# breakbeam-interface.net
KiCad netlist of a schematic drawn in Altium Designer
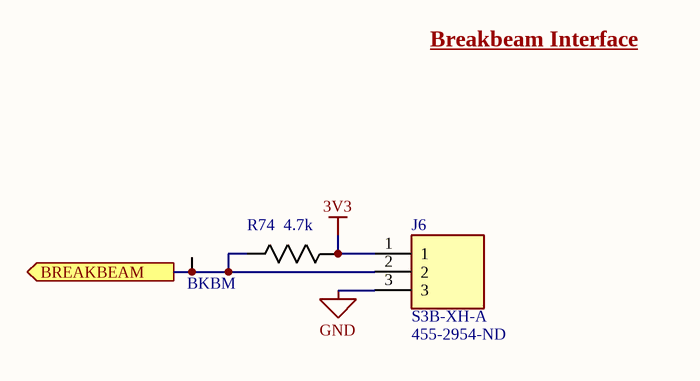
[diagram p0: breakbeam-interface.SchDoc]

(export (version "E")
  (design (tool "Eeschema 10.0.6"))
  (components
    (comp (ref "BKBM")
      (value "Test Point (Via)")
      (footprint "TP")
      (libsource (lib "IC_Library") (part "Test Point (Via)"))
    )
    (comp (ref "J6")
      (value "S3B-XH-A")
      (footprint "JST_S3B-XH-A")
      (description "Connector Header Through Hole Right Angle 3 position 0.098 (2.50mm)")
      (fields
        (field (name "MF") "JST Sales")
        (field (name "MP") "B3B-XH-A(LF)(SN)")
        (field (name "SUPPLIER PART NUMBER 1") "455-2954-ND")
      )
      (libsource (lib "Connector_Library") (part "CN HDR 3POS JST XH RA"))
    )
    (comp (ref "R74")
      (value "4.7k")
      (footprint "0603")
      (description "RES SMD 4.7k OHM 5% 1/8W 0603")
      (fields (field (name "TOLERANCE") "5%") (field (name "PART NUMBER") "RES 4.7k 1/8W - 5%"))
      (libsource (lib "Resistor_Library") (part "RES 4.7k 1/8W - 5%"))
    )
  )
  (nets
    (net (code "1") (name "/BREAKBEAM") (class "Default")
      (node (ref "BKBM") (pin "1") (pinfunction "1_1") (pintype "passive"))
      (node (ref "J6") (pin "2") (pinfunction "2_2") (pintype "passive"))
      (node (ref "R74") (pin "2") (pinfunction "R2_2") (pintype "passive"))
    )
    (net (code "2") (name "3V3") (class "Default")
      (node (ref "J6") (pin "1") (pinfunction "1_1") (pintype "passive"))
      (node (ref "R74") (pin "1") (pinfunction "R1_1") (pintype "passive"))
    )
    (net (code "3") (name "GND") (class "Default")
      (node (ref "J6") (pin "3") (pinfunction "3_3") (pintype "passive"))
    )
  )
)
